# iobbq_solar_charger.net
KiCad netlist of a schematic drawn in EAGLE
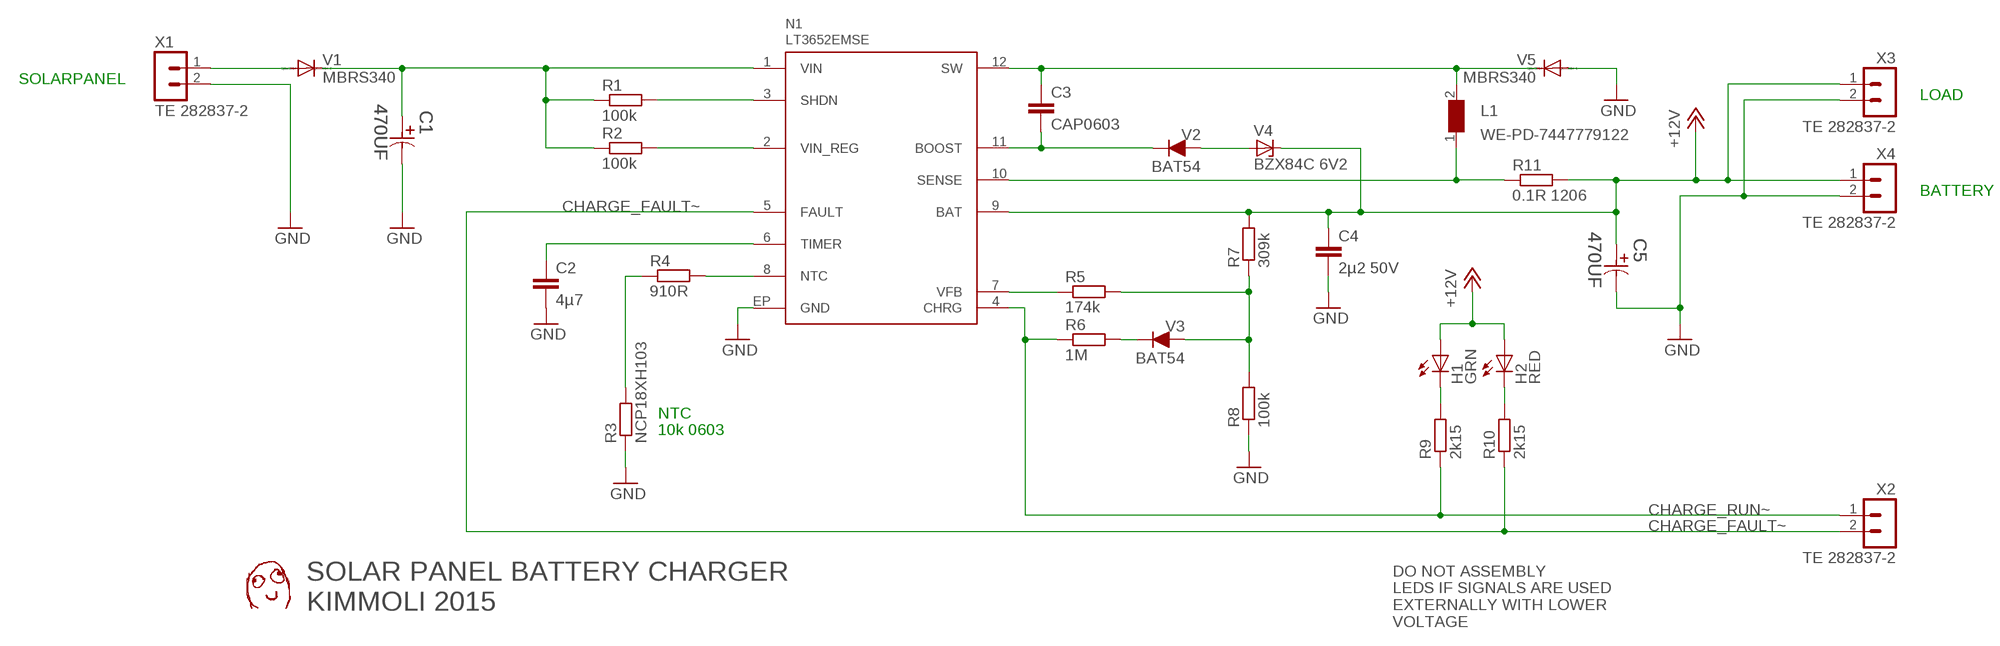
[diagram p0: schematic, sheet 1]

(export (version "E")
  (design (tool "Eeschema 10.0.6"))
  (components
    (comp (ref "C1")
      (value "470UF")
      (footprint "eagle-import:CAPAE1350X1400N")
      (fields (field (name "MPN") "EEVFK1V471Q") (field (name "TOLERANCE") "±20 %"))
      (libsource (lib "eagle-import") (part "EEV--CASE-H13FK1V471Q"))
    )
    (comp (ref "C2")
      (value "4µ7")
      (footprint "eagle-import:C0805")
      (libsource (lib "eagle-import") (part "CAP0805"))
    )
    (comp (ref "C3")
      (value "CAP0603")
      (footprint "eagle-import:C0603")
      (libsource (lib "eagle-import") (part "CAP0603"))
    )
    (comp (ref "C4")
      (value "2µ2 50V")
      (footprint "eagle-import:C0805")
      (libsource (lib "eagle-import") (part "CAP0805"))
    )
    (comp (ref "C5")
      (value "470UF")
      (footprint "eagle-import:CAPAE1350X1400N")
      (fields (field (name "MPN") "EEVFK1V471Q") (field (name "TOLERANCE") "±20 %"))
      (libsource (lib "eagle-import") (part "EEV--CASE-H13FK1V471Q"))
    )
    (comp (ref "H1")
      (value "GRN")
      (footprint "eagle-import:LED3MM")
      (libsource (lib "eagle-import") (part "LED3MM"))
    )
    (comp (ref "H2")
      (value "RED")
      (footprint "eagle-import:LED3MM")
      (libsource (lib "eagle-import") (part "LED3MM"))
    )
    (comp (ref "L1")
      (value "WE-PD-7447779122")
      (footprint "eagle-import:WE-PD_7332_7345_PLASTIC_BASE")
      (fields (field (name "MPN") "7447779122"))
      (libsource (lib "eagle-import") (part "WE-PD_7332/7345_PLASTIC_BASE-7447779122"))
    )
    (comp (ref "N1")
      (value "LT3652EMSE")
      (footprint "eagle-import:MSOP-12-EP-065")
      (libsource (lib "eagle-import") (part "LT3652EMSE"))
    )
    (comp (ref "R1")
      (value "100k")
      (footprint "eagle-import:R0603")
      (libsource (lib "eagle-import") (part "RES0603"))
    )
    (comp (ref "R2")
      (value "100k")
      (footprint "eagle-import:R0603")
      (libsource (lib "eagle-import") (part "RES0603"))
    )
    (comp (ref "R3")
      (value "NCP18XH103")
      (footprint "eagle-import:R0603")
      (libsource (lib "eagle-import") (part "RES0603"))
    )
    (comp (ref "R4")
      (value "910R")
      (footprint "eagle-import:R0603")
      (libsource (lib "eagle-import") (part "RES0603"))
    )
    (comp (ref "R5")
      (value "174k")
      (footprint "eagle-import:R0603")
      (libsource (lib "eagle-import") (part "RES0603"))
    )
    (comp (ref "R6")
      (value "1M")
      (footprint "eagle-import:R0603")
      (libsource (lib "eagle-import") (part "RES0603"))
    )
    (comp (ref "R7")
      (value "309k")
      (footprint "eagle-import:R0603")
      (libsource (lib "eagle-import") (part "RES0603"))
    )
    (comp (ref "R8")
      (value "100k")
      (footprint "eagle-import:R0603")
      (libsource (lib "eagle-import") (part "RES0603"))
    )
    (comp (ref "R9")
      (value "2k15")
      (footprint "eagle-import:R1206")
      (libsource (lib "eagle-import") (part "RES1206"))
    )
    (comp (ref "R10")
      (value "2k15")
      (footprint "eagle-import:R1206")
      (libsource (lib "eagle-import") (part "RES1206"))
    )
    (comp (ref "R11")
      (value "0.1R 1206")
      (footprint "eagle-import:R1206")
      (libsource (lib "eagle-import") (part "RES1206"))
    )
    (comp (ref "U$2")
      (value "DAFUG")
      (footprint "eagle-import:DAFUG")
      (libsource (lib "eagle-import") (part "DAFUG"))
    )
    (comp (ref "V1")
      (value "MBRS340")
      (footprint "eagle-import:SMC")
      (libsource (lib "eagle-import") (part "DIODE-SMC"))
    )
    (comp (ref "V2")
      (value "BAT54")
      (footprint "eagle-import:SOT23")
      (libsource (lib "eagle-import") (part "BAT54"))
    )
    (comp (ref "V3")
      (value "BAT54")
      (footprint "eagle-import:SOT23")
      (libsource (lib "eagle-import") (part "BAT54"))
    )
    (comp (ref "V4")
      (value "BZX84C 6V2")
      (footprint "eagle-import:TO236")
      (libsource (lib "eagle-import") (part "BZX84CSMD"))
    )
    (comp (ref "V5")
      (value "MBRS340")
      (footprint "eagle-import:SMC")
      (libsource (lib "eagle-import") (part "DIODE-SMC"))
    )
    (comp (ref "X1")
      (value "TE 282837-2")
      (footprint "eagle-import:TE_RUUVILIITIN2")
      (libsource (lib "eagle-import") (part "TE_RUUVILIITIN2"))
    )
    (comp (ref "X2")
      (value "TE 282837-2")
      (footprint "eagle-import:TE_RUUVILIITIN2")
      (libsource (lib "eagle-import") (part "TE_RUUVILIITIN2"))
    )
    (comp (ref "X3")
      (value "TE 282837-2")
      (footprint "eagle-import:TE_RUUVILIITIN2")
      (libsource (lib "eagle-import") (part "TE_RUUVILIITIN2"))
    )
    (comp (ref "X4")
      (value "TE 282837-2")
      (footprint "eagle-import:TE_RUUVILIITIN2")
      (libsource (lib "eagle-import") (part "TE_RUUVILIITIN2"))
    )
  )
  (nets
    (net (code "1") (name "+12V") (class "Default")
      (node (ref "C4") (pin "1") (pinfunction "1_1") (pintype "passive"))
      (node (ref "C5") (pin "1") (pinfunction "1_1") (pintype "passive"))
      (node (ref "H1") (pin "A") (pinfunction "A_A") (pintype "passive"))
      (node (ref "H2") (pin "A") (pinfunction "A_A") (pintype "passive"))
      (node (ref "N1") (pin "9") (pinfunction "BAT_9") (pintype "bidirectional"))
      (node (ref "R11") (pin "2") (pinfunction "2_2") (pintype "passive"))
      (node (ref "R7") (pin "2") (pinfunction "2_2") (pintype "passive"))
      (node (ref "V4") (pin "C") (pinfunction "C_C") (pintype "passive"))
      (node (ref "X3") (pin "1") (pinfunction "1_1") (pintype "passive"))
      (node (ref "X4") (pin "1") (pinfunction "1_1") (pintype "passive"))
    )
    (net (code "2") (name "/CHARGE_FAULT~{}") (class "Default")
      (node (ref "N1") (pin "5") (pinfunction "FAULT_5") (pintype "bidirectional"))
      (node (ref "R10") (pin "1") (pinfunction "1_1") (pintype "passive"))
      (node (ref "X2") (pin "2") (pinfunction "2_2") (pintype "passive"))
    )
    (net (code "3") (name "/CHARGE_RUN~{}") (class "Default")
      (node (ref "N1") (pin "4") (pinfunction "CHRG_4") (pintype "bidirectional"))
      (node (ref "R6") (pin "1") (pinfunction "1_1") (pintype "passive"))
      (node (ref "R9") (pin "1") (pinfunction "1_1") (pintype "passive"))
      (node (ref "X2") (pin "1") (pinfunction "1_1") (pintype "passive"))
    )
    (net (code "4") (name "GND") (class "Default")
      (node (ref "C1") (pin "2") (pinfunction "2_2") (pintype "passive"))
      (node (ref "C2") (pin "2") (pinfunction "2_2") (pintype "passive"))
      (node (ref "C4") (pin "2") (pinfunction "2_2") (pintype "passive"))
      (node (ref "C5") (pin "2") (pinfunction "2_2") (pintype "passive"))
      (node (ref "N1") (pin "EP") (pinfunction "GND_EP") (pintype "bidirectional"))
      (node (ref "R3") (pin "1") (pinfunction "1_1") (pintype "passive"))
      (node (ref "R8") (pin "1") (pinfunction "1_1") (pintype "passive"))
      (node (ref "V5") (pin "A") (pinfunction "A_A") (pintype "passive"))
      (node (ref "X1") (pin "2") (pinfunction "2_2") (pintype "passive"))
      (node (ref "X3") (pin "2") (pinfunction "2_2") (pintype "passive"))
      (node (ref "X4") (pin "2") (pinfunction "2_2") (pintype "passive"))
    )
    (net (code "5") (name "Net-(H1-C)") (class "Default")
      (node (ref "H1") (pin "K") (pinfunction "C_K") (pintype "passive"))
      (node (ref "R9") (pin "2") (pinfunction "2_2") (pintype "passive"))
    )
    (net (code "6") (name "Net-(H2-C)") (class "Default")
      (node (ref "H2") (pin "K") (pinfunction "C_K") (pintype "passive"))
      (node (ref "R10") (pin "2") (pinfunction "2_2") (pintype "passive"))
    )
    (net (code "7") (name "Net-(N1-BOOST)") (class "Default")
      (node (ref "C3") (pin "2") (pinfunction "2_2") (pintype "passive"))
      (node (ref "N1") (pin "11") (pinfunction "BOOST_11") (pintype "bidirectional"))
      (node (ref "V2") (pin "3") (pinfunction "3_3") (pintype "bidirectional"))
    )
    (net (code "8") (name "Net-(N1-NTC)") (class "Default")
      (node (ref "N1") (pin "8") (pinfunction "NTC_8") (pintype "bidirectional"))
      (node (ref "R4") (pin "2") (pinfunction "2_2") (pintype "passive"))
    )
    (net (code "9") (name "Net-(N1-SENSE)") (class "Default")
      (node (ref "L1") (pin "1") (pinfunction "1_1") (pintype "passive"))
      (node (ref "N1") (pin "10") (pinfunction "SENSE_10") (pintype "bidirectional"))
      (node (ref "R11") (pin "1") (pinfunction "1_1") (pintype "passive"))
    )
    (net (code "10") (name "Net-(N1-SHDN)") (class "Default")
      (node (ref "N1") (pin "3") (pinfunction "SHDN_3") (pintype "bidirectional"))
      (node (ref "R1") (pin "2") (pinfunction "2_2") (pintype "passive"))
    )
    (net (code "11") (name "Net-(N1-SW)") (class "Default")
      (node (ref "C3") (pin "1") (pinfunction "1_1") (pintype "passive"))
      (node (ref "L1") (pin "2") (pinfunction "2_2") (pintype "passive"))
      (node (ref "N1") (pin "12") (pinfunction "SW_12") (pintype "bidirectional"))
      (node (ref "V5") (pin "C") (pinfunction "C_C") (pintype "passive"))
    )
    (net (code "12") (name "Net-(N1-TIMER)") (class "Default")
      (node (ref "C2") (pin "1") (pinfunction "1_1") (pintype "passive"))
      (node (ref "N1") (pin "6") (pinfunction "TIMER_6") (pintype "bidirectional"))
    )
    (net (code "13") (name "Net-(N1-VFB)") (class "Default")
      (node (ref "N1") (pin "7") (pinfunction "VFB_7") (pintype "bidirectional"))
      (node (ref "R5") (pin "1") (pinfunction "1_1") (pintype "passive"))
    )
    (net (code "14") (name "Net-(N1-VIN)") (class "Default")
      (node (ref "C1") (pin "1") (pinfunction "1_1") (pintype "passive"))
      (node (ref "N1") (pin "1") (pinfunction "VIN_1") (pintype "bidirectional"))
      (node (ref "R1") (pin "1") (pinfunction "1_1") (pintype "passive"))
      (node (ref "R2") (pin "1") (pinfunction "1_1") (pintype "passive"))
      (node (ref "V1") (pin "C") (pinfunction "C_C") (pintype "passive"))
    )
    (net (code "15") (name "Net-(N1-VIN_REG)") (class "Default")
      (node (ref "N1") (pin "2") (pinfunction "VIN_REG_2") (pintype "bidirectional"))
      (node (ref "R2") (pin "2") (pinfunction "2_2") (pintype "passive"))
    )
    (net (code "16") (name "Net-(R3-Pad2)") (class "Default")
      (node (ref "R3") (pin "2") (pinfunction "2_2") (pintype "passive"))
      (node (ref "R4") (pin "1") (pinfunction "1_1") (pintype "passive"))
    )
    (net (code "17") (name "Net-(R5-Pad2)") (class "Default")
      (node (ref "R5") (pin "2") (pinfunction "2_2") (pintype "passive"))
      (node (ref "R7") (pin "1") (pinfunction "1_1") (pintype "passive"))
      (node (ref "R8") (pin "2") (pinfunction "2_2") (pintype "passive"))
      (node (ref "V3") (pin "1") (pinfunction "1_1") (pintype "bidirectional"))
    )
    (net (code "18") (name "Net-(R6-Pad2)") (class "Default")
      (node (ref "R6") (pin "2") (pinfunction "2_2") (pintype "passive"))
      (node (ref "V3") (pin "3") (pinfunction "3_3") (pintype "bidirectional"))
    )
    (net (code "19") (name "Net-(V1-PadA)") (class "Default")
      (node (ref "V1") (pin "A") (pinfunction "A_A") (pintype "passive"))
      (node (ref "X1") (pin "1") (pinfunction "1_1") (pintype "passive"))
    )
    (net (code "20") (name "Net-(V2-Pad1)") (class "Default")
      (node (ref "V2") (pin "1") (pinfunction "1_1") (pintype "bidirectional"))
      (node (ref "V4") (pin "A") (pinfunction "A_A") (pintype "passive"))
    )
  )
)
